# openmv.net
KiCad netlist of a schematic drawn in EAGLE
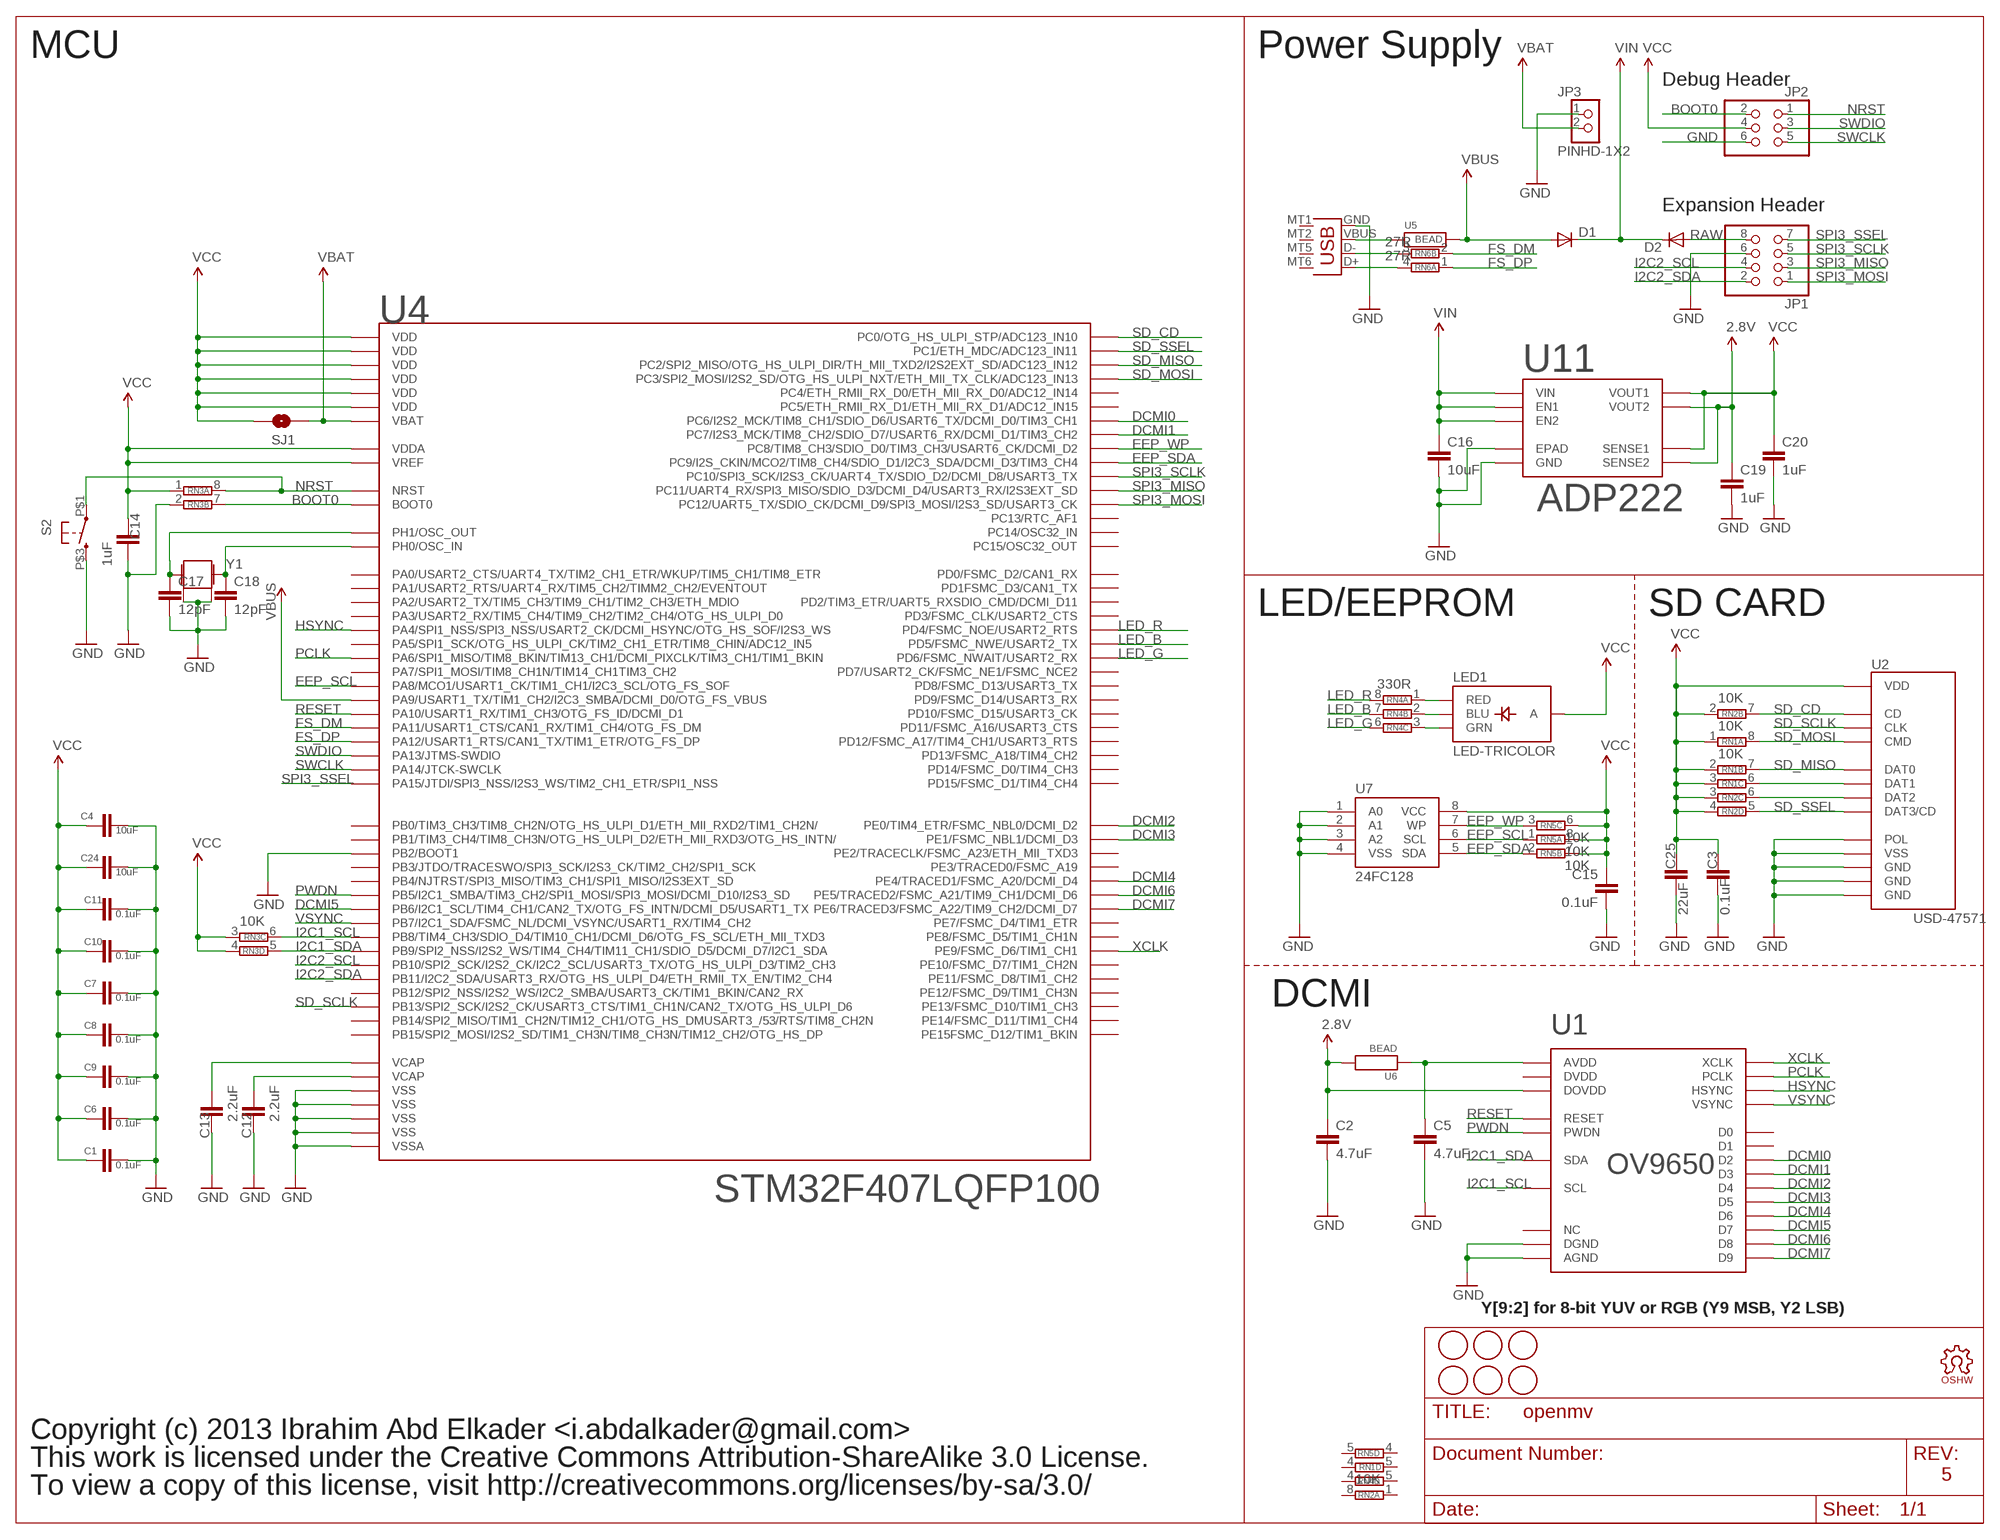
[diagram p0: schematic, sheet 1]

(export (version "E")
  (design (tool "Eeschema 10.0.6"))
  (components
    (comp (ref "C1")
      (value "0.1uF")
      (footprint "eagle-import:0402-CAP")
      (libsource (lib "eagle-import") (part "CAP0402-CAP"))
    )
    (comp (ref "C2")
      (value "4.7uF")
      (footprint "eagle-import:0402-CAP")
      (libsource (lib "eagle-import") (part "CAP0402-CAP"))
    )
    (comp (ref "C3")
      (value "0.1uF")
      (footprint "eagle-import:0402-CAP")
      (libsource (lib "eagle-import") (part "CAP0402-CAP"))
    )
    (comp (ref "C4")
      (value "10uF")
      (footprint "eagle-import:0805")
      (libsource (lib "eagle-import") (part "CAP0805"))
    )
    (comp (ref "C5")
      (value "4.7uF")
      (footprint "eagle-import:0402-CAP")
      (libsource (lib "eagle-import") (part "CAP0402-CAP"))
    )
    (comp (ref "C6")
      (value "0.1uF")
      (footprint "eagle-import:0402-CAP")
      (libsource (lib "eagle-import") (part "CAP0402-CAP"))
    )
    (comp (ref "C7")
      (value "0.1uF")
      (footprint "eagle-import:0402-CAP")
      (libsource (lib "eagle-import") (part "CAP0402-CAP"))
    )
    (comp (ref "C8")
      (value "0.1uF")
      (footprint "eagle-import:0402-CAP")
      (libsource (lib "eagle-import") (part "CAP0402-CAP"))
    )
    (comp (ref "C9")
      (value "0.1uF")
      (footprint "eagle-import:0402-CAP")
      (libsource (lib "eagle-import") (part "CAP0402-CAP"))
    )
    (comp (ref "C10")
      (value "0.1uF")
      (footprint "eagle-import:0402-CAP")
      (libsource (lib "eagle-import") (part "CAP0402-CAP"))
    )
    (comp (ref "C11")
      (value "0.1uF")
      (footprint "eagle-import:0402-CAP")
      (libsource (lib "eagle-import") (part "CAP0402-CAP"))
    )
    (comp (ref "C12")
      (value "2.2uF")
      (footprint "eagle-import:0402-CAP")
      (libsource (lib "eagle-import") (part "CAP0402-CAP"))
    )
    (comp (ref "C13")
      (value "2.2uF")
      (footprint "eagle-import:0402-CAP")
      (libsource (lib "eagle-import") (part "CAP0402-CAP"))
    )
    (comp (ref "C14")
      (value "1uF")
      (footprint "eagle-import:0402-CAP")
      (libsource (lib "eagle-import") (part "CAP0402-CAP"))
    )
    (comp (ref "C15")
      (value "0.1uF")
      (footprint "eagle-import:0402-CAP")
      (libsource (lib "eagle-import") (part "CAP0402-CAP"))
    )
    (comp (ref "C16")
      (value "10uF")
      (footprint "eagle-import:0805")
      (libsource (lib "eagle-import") (part "CAP0805"))
    )
    (comp (ref "C17")
      (value "12pF")
      (footprint "eagle-import:0402-CAP")
      (libsource (lib "eagle-import") (part "CAP0402-CAP"))
    )
    (comp (ref "C18")
      (value "12pF")
      (footprint "eagle-import:0402-CAP")
      (libsource (lib "eagle-import") (part "CAP0402-CAP"))
    )
    (comp (ref "C19")
      (value "1uF")
      (footprint "eagle-import:0402-CAP")
      (libsource (lib "eagle-import") (part "CAP0402-CAP"))
    )
    (comp (ref "C20")
      (value "1uF")
      (footprint "eagle-import:0402-CAP")
      (libsource (lib "eagle-import") (part "CAP0402-CAP"))
    )
    (comp (ref "C24")
      (value "10uF")
      (footprint "eagle-import:0805")
      (libsource (lib "eagle-import") (part "CAP0805"))
    )
    (comp (ref "C25")
      (value "22uF")
      (footprint "eagle-import:0805")
      (libsource (lib "eagle-import") (part "CAP0805"))
    )
    (comp (ref "D1")
      (value "DIODESOD")
      (footprint "eagle-import:SOD-323")
      (libsource (lib "eagle-import") (part "DIODESOD"))
    )
    (comp (ref "D2")
      (value "DIODESOD")
      (footprint "eagle-import:SOD-323")
      (libsource (lib "eagle-import") (part "DIODESOD"))
    )
    (comp (ref "JP1")
      (value "PINHD-2X4")
      (footprint "eagle-import:2X04")
      (libsource (lib "eagle-import") (part "PINHD-2X4"))
    )
    (comp (ref "JP2")
      (value "PINHD-2X3")
      (footprint "eagle-import:2X03")
      (libsource (lib "eagle-import") (part "PINHD-2X3"))
    )
    (comp (ref "JP3")
      (value "PINHD-1X2")
      (footprint "eagle-import:1X2")
      (libsource (lib "eagle-import") (part "PINHD-1X2"))
    )
    (comp (ref "LED1")
      (value "LED-TRICOLOR")
      (footprint "eagle-import:LED-TRICOLOR-SMD")
      (libsource (lib "eagle-import") (part "LED-TRICOLOR"))
    )
    (comp (ref "LOGO1")
      (value "OSHW_LOGO_FILLX0150-NT")
      (footprint "eagle-import:OSHW_FILLX150_NOTEXT")
      (libsource (lib "eagle-import") (part "OSHW_LOGO_FILLX0150-NT"))
    )
    (comp (ref "RN1")
      (value "10K")
      (footprint "eagle-import:CAT16")
      (fields (field (name "OC_FARNELL") "unknown") (field (name "OC_NEWARK") "unknown"))
      (libsource (lib "eagle-import") (part "4R-NCAT16"))
    )
    (comp (ref "RN2")
      (value "10K")
      (footprint "eagle-import:CAT16")
      (fields (field (name "OC_FARNELL") "unknown") (field (name "OC_NEWARK") "unknown"))
      (libsource (lib "eagle-import") (part "4R-NCAT16"))
    )
    (comp (ref "RN3")
      (value "10K")
      (footprint "eagle-import:CAT16")
      (libsource (lib "eagle-import") (part "4R-NCAT16"))
    )
    (comp (ref "RN4")
      (value "330R")
      (footprint "eagle-import:CAT16")
      (fields (field (name "OC_FARNELL") "unknown") (field (name "OC_NEWARK") "unknown"))
      (libsource (lib "eagle-import") (part "4R-NCAT16"))
    )
    (comp (ref "RN5")
      (value "10K")
      (footprint "eagle-import:CAT16")
      (fields (field (name "OC_FARNELL") "unknown") (field (name "OC_NEWARK") "unknown"))
      (libsource (lib "eagle-import") (part "4R-NCAT16"))
    )
    (comp (ref "RN6")
      (value "27R")
      (footprint "eagle-import:EXBV4V")
      (libsource (lib "eagle-import") (part "2R-NEXBV4V"))
    )
    (comp (ref "S2")
      (value "SWITCHKMR442G")
      (footprint "eagle-import:KMR442G")
      (libsource (lib "eagle-import") (part "SWITCHKMR442G"))
    )
    (comp (ref "SJ1")
      (value "SOLDERJUMPERTRACE")
      (footprint "eagle-import:SJ_2S-TRACE")
      (libsource (lib "eagle-import") (part "SOLDERJUMPERTRACE"))
    )
    (comp (ref "U$3")
      (value "FIDUCIAL")
      (footprint "eagle-import:FIDUCIAL_1MM")
      (libsource (lib "eagle-import") (part "FIDUCIAL"))
    )
    (comp (ref "U$4")
      (value "FIDUCIAL")
      (footprint "eagle-import:FIDUCIAL_1MM")
      (libsource (lib "eagle-import") (part "FIDUCIAL"))
    )
    (comp (ref "U$5")
      (value "FIDUCIAL")
      (footprint "eagle-import:FIDUCIAL_1MM")
      (libsource (lib "eagle-import") (part "FIDUCIAL"))
    )
    (comp (ref "U$7")
      (value "FIDUCIAL")
      (footprint "eagle-import:FIDUCIAL_1MM")
      (libsource (lib "eagle-import") (part "FIDUCIAL"))
    )
    (comp (ref "U$9")
      (value "FIDUCIAL")
      (footprint "eagle-import:FIDUCIAL_1MM")
      (libsource (lib "eagle-import") (part "FIDUCIAL"))
    )
    (comp (ref "U$10")
      (value "FIDUCIAL")
      (footprint "eagle-import:FIDUCIAL_1MM")
      (libsource (lib "eagle-import") (part "FIDUCIAL"))
    )
    (comp (ref "U1")
      (value "OV9650")
      (footprint "eagle-import:OV9650")
      (libsource (lib "eagle-import") (part "OV9650"))
    )
    (comp (ref "U2")
      (value "USD-47571")
      (footprint "eagle-import:USD-47571")
      (libsource (lib "eagle-import") (part "USD-47571"))
    )
    (comp (ref "U4")
      (value "STM32F407LQFP100")
      (footprint "eagle-import:LQFP100")
      (libsource (lib "eagle-import") (part "STM32F407LQFP100"))
    )
    (comp (ref "U5")
      (value "BEAD")
      (footprint "eagle-import:0402-CAP")
      (libsource (lib "eagle-import") (part "BEAD"))
    )
    (comp (ref "U6")
      (value "BEAD")
      (footprint "eagle-import:0402-CAP")
      (libsource (lib "eagle-import") (part "BEAD"))
    )
    (comp (ref "U7")
      (value "24FC128")
      (footprint "eagle-import:MSOP8")
      (libsource (lib "eagle-import") (part "24FC128"))
    )
    (comp (ref "U11")
      (value "ADP222")
      (footprint "eagle-import:LFCSP8")
      (libsource (lib "eagle-import") (part "ADP222"))
    )
    (comp (ref "X1")
      (value "USB-MICROB")
      (footprint "eagle-import:USB-MICROB")
      (libsource (lib "eagle-import") (part "USB-MICROB"))
    )
    (comp (ref "Y1")
      (value "CRYSTAL2.5X2.0")
      (footprint "eagle-import:CRYSTAL-2.5X2.0")
      (libsource (lib "eagle-import") (part "CRYSTAL2.5X2.0"))
    )
  )
  (nets
    (net (code "1") (name "/BOOT0") (class "Default")
      (node (ref "JP2") (pin "2") (pinfunction "2_2") (pintype "passive"))
      (node (ref "RN3") (pin "7") (pinfunction "2_7") (pintype "passive"))
      (node (ref "U4") (pin "94") (pinfunction "BOOT0_94") (pintype "bidirectional"))
    )
    (net (code "2") (name "/DCMI0") (class "Default")
      (node (ref "U1") (pin "P$19") (pinfunction "D2_P$19") (pintype "bidirectional"))
      (node (ref "U4") (pin "63") (pinfunction "PC6/I2S2_MCK/TIM8_CH1/SDIO_D6/USART6_TX/DCMI_D0/TIM3_CH1_63") (pintype "bidirectional"))
    )
    (net (code "3") (name "/DCMI1") (class "Default")
      (node (ref "U1") (pin "P$21") (pinfunction "D3_P$21") (pintype "bidirectional"))
      (node (ref "U4") (pin "64") (pinfunction "PC7/I2S3_MCK/TIM8_CH2/SDIO_D7/USART6_RX/DCMI_D1/TIM3_CH2_64") (pintype "bidirectional"))
    )
    (net (code "4") (name "/DCMI2") (class "Default")
      (node (ref "U1") (pin "P$22") (pinfunction "D4_P$22") (pintype "bidirectional"))
      (node (ref "U4") (pin "97") (pinfunction "PE0/TIM4_ETR/FSMC_NBL0/DCMI_D2_97") (pintype "bidirectional"))
    )
    (net (code "5") (name "/DCMI3") (class "Default")
      (node (ref "U1") (pin "P$20") (pinfunction "D5_P$20") (pintype "bidirectional"))
      (node (ref "U4") (pin "98") (pinfunction "PE1/FSMC_NBL1/DCMI_D3_98") (pintype "bidirectional"))
    )
    (net (code "6") (name "/DCMI4") (class "Default")
      (node (ref "U1") (pin "P$18") (pinfunction "D6_P$18") (pintype "bidirectional"))
      (node (ref "U4") (pin "3") (pinfunction "PE4/TRACED1/FSMC_A20/DCMI_D4_3") (pintype "bidirectional"))
    )
    (net (code "7") (name "/DCMI5") (class "Default")
      (node (ref "U1") (pin "P$16") (pinfunction "D7_P$16") (pintype "bidirectional"))
      (node (ref "U4") (pin "92") (pinfunction "PB6/I2C1_SCL/TIM4_CH1/CAN2_TX/OTG_FS_INTN/DCMI_D5/USART1_TX_92") (pintype "bidirectional"))
    )
    (net (code "8") (name "/DCMI6") (class "Default")
      (node (ref "U1") (pin "P$14") (pinfunction "D8_P$14") (pintype "bidirectional"))
      (node (ref "U4") (pin "4") (pinfunction "PE5/TRACED2/FSMC_A21/TIM9_CH1/DCMI_D6_4") (pintype "bidirectional"))
    )
    (net (code "9") (name "/DCMI7") (class "Default")
      (node (ref "U1") (pin "P$12") (pinfunction "D9_P$12") (pintype "bidirectional"))
      (node (ref "U4") (pin "5") (pinfunction "PE6/TRACED3/FSMC_A22/TIM9_CH2/DCMI_D7_5") (pintype "bidirectional"))
    )
    (net (code "10") (name "/EEP_SCL") (class "Default")
      (node (ref "RN5") (pin "1") (pinfunction "1_1") (pintype "passive"))
      (node (ref "U4") (pin "67") (pinfunction "PA8/MCO1/USART1_CK/TIM1_CH1/I2C3_SCL/OTG_FS_SOF_67") (pintype "bidirectional"))
      (node (ref "U7") (pin "6") (pinfunction "SCL_6") (pintype "bidirectional"))
    )
    (net (code "11") (name "/EEP_SDA") (class "Default")
      (node (ref "RN5") (pin "2") (pinfunction "1_2") (pintype "passive"))
      (node (ref "U4") (pin "66") (pinfunction "PC9/I2S_CKIN/MCO2/TIM8_CH4/SDIO_D1/I2C3_SDA/DCMI_D3/TIM3_CH4_66") (pintype "bidirectional"))
      (node (ref "U7") (pin "5") (pinfunction "SDA_5") (pintype "bidirectional"))
    )
    (net (code "12") (name "/EEP_WP") (class "Default")
      (node (ref "RN5") (pin "3") (pinfunction "1_3") (pintype "passive"))
      (node (ref "U4") (pin "65") (pinfunction "PC8/TIM8_CH3/SDIO_D0/TIM3_CH3/USART6_CK/DCMI_D2_65") (pintype "bidirectional"))
      (node (ref "U7") (pin "7") (pinfunction "WP_7") (pintype "bidirectional"))
    )
    (net (code "13") (name "/FS_DM") (class "Default")
      (node (ref "RN6") (pin "2") (pinfunction "1_2") (pintype "passive"))
      (node (ref "U4") (pin "70") (pinfunction "PA11/USART1_CTS/CAN1_RX/TIM1_CH4/OTG_FS_DM_70") (pintype "bidirectional"))
    )
    (net (code "14") (name "/FS_DP") (class "Default")
      (node (ref "RN6") (pin "1") (pinfunction "1_1") (pintype "passive"))
      (node (ref "U4") (pin "71") (pinfunction "PA12/USART1_RTS/CAN1_TX/TIM1_ETR/OTG_FS_DP_71") (pintype "bidirectional"))
    )
    (net (code "15") (name "/HSYNC") (class "Default")
      (node (ref "U1") (pin "P$9") (pinfunction "HSYNC_P$9") (pintype "bidirectional"))
      (node (ref "U4") (pin "29") (pinfunction "PA4/SPI1_NSS/SPI3_NSS/USART2_CK/DCMI_HSYNC/OTG_HS_SOF/I2S3_WS_29") (pintype "bidirectional"))
    )
    (net (code "16") (name "/I2C1_SCL") (class "Default")
      (node (ref "RN3") (pin "6") (pinfunction "2_6") (pintype "passive"))
      (node (ref "U1") (pin "P$5") (pinfunction "SCL_P$5") (pintype "bidirectional"))
      (node (ref "U4") (pin "95") (pinfunction "PB8/TIM4_CH3/SDIO_D4/TIM10_CH1/DCMI_D6/OTG_FS_SCL/ETH_MII_TXD3_95") (pintype "bidirectional"))
    )
    (net (code "17") (name "/I2C1_SDA") (class "Default")
      (node (ref "RN3") (pin "5") (pinfunction "2_5") (pintype "passive"))
      (node (ref "U1") (pin "P$3") (pinfunction "SDA_P$3") (pintype "bidirectional"))
      (node (ref "U4") (pin "96") (pinfunction "PB9/SPI2_NSS/I2S2_WS/TIM4_CH4/TIM11_CH1/SDIO_D5/DCMI_D7/I2C1_SDA_96") (pintype "bidirectional"))
    )
    (net (code "18") (name "/I2C2_SCL") (class "Default")
      (node (ref "JP1") (pin "4") (pinfunction "4_4") (pintype "passive"))
      (node (ref "U4") (pin "47") (pinfunction "PB10/SPI2_SCK/I2S2_CK/I2C2_SCL/USART3_TX/OTG_HS_ULPI_D3/TIM2_CH3_47") (pintype "bidirectional"))
    )
    (net (code "19") (name "/I2C2_SDA") (class "Default")
      (node (ref "JP1") (pin "2") (pinfunction "2_2") (pintype "passive"))
      (node (ref "U4") (pin "48") (pinfunction "PB11/I2C2_SDA/USART3_RX/OTG_HS_ULPI_D4/ETH_RMII_TX_EN/TIM2_CH4_48") (pintype "bidirectional"))
    )
    (net (code "20") (name "/LED_B") (class "Default")
      (node (ref "RN4") (pin "7") (pinfunction "2_7") (pintype "passive"))
      (node (ref "U4") (pin "86") (pinfunction "PD5/FSMC_NWE/USART2_TX_86") (pintype "bidirectional"))
    )
    (net (code "21") (name "/LED_G") (class "Default")
      (node (ref "RN4") (pin "6") (pinfunction "2_6") (pintype "passive"))
      (node (ref "U4") (pin "87") (pinfunction "PD6/FSMC_NWAIT/USART2_RX_87") (pintype "bidirectional"))
    )
    (net (code "22") (name "/LED_R") (class "Default")
      (node (ref "RN4") (pin "8") (pinfunction "2_8") (pintype "passive"))
      (node (ref "U4") (pin "85") (pinfunction "PD4/FSMC_NOE/USART2_RTS_85") (pintype "bidirectional"))
    )
    (net (code "23") (name "/NRST") (class "Default")
      (node (ref "JP2") (pin "1") (pinfunction "1_1") (pintype "passive"))
      (node (ref "RN3") (pin "8") (pinfunction "2_8") (pintype "passive"))
      (node (ref "S2") (pin "P$1") (pinfunction "1_P$1") (pintype "passive"))
      (node (ref "U4") (pin "14") (pinfunction "NRST_14") (pintype "bidirectional"))
    )
    (net (code "24") (name "/PCLK") (class "Default")
      (node (ref "U1") (pin "P$17") (pinfunction "PCLK_P$17") (pintype "bidirectional"))
      (node (ref "U4") (pin "31") (pinfunction "PA6/SPI1_MISO/TIM8_BKIN/TIM13_CH1/DCMI_PIXCLK/TIM3_CH1/TIM1_BKIN_31") (pintype "bidirectional"))
    )
    (net (code "25") (name "/PWDN") (class "Default")
      (node (ref "U1") (pin "P$8") (pinfunction "PWDN_P$8") (pintype "bidirectional"))
      (node (ref "U4") (pin "91") (pinfunction "PB5/I2C1_SMBA/TIM3_CH2/SPI1_MOSI/SPI3_MOSI/DCMI_D10/I2S3_SD_91") (pintype "bidirectional"))
    )
    (net (code "26") (name "/RAW") (class "Default")
      (node (ref "D2") (pin "2") (pinfunction "A_2") (pintype "passive"))
      (node (ref "JP1") (pin "8") (pinfunction "8_8") (pintype "passive"))
    )
    (net (code "27") (name "/RESET") (class "Default")
      (node (ref "U1") (pin "P$6") (pinfunction "RESET_P$6") (pintype "bidirectional"))
      (node (ref "U4") (pin "69") (pinfunction "PA10/USART1_RX/TIM1_CH3/OTG_FS_ID/DCMI_D1_69") (pintype "bidirectional"))
    )
    (net (code "28") (name "/SD_CD") (class "Default")
      (node (ref "RN2") (pin "7") (pinfunction "2_7") (pintype "passive"))
      (node (ref "U2") (pin "G$5") (pinfunction "CD_G$5") (pintype "power_in"))
      (node (ref "U4") (pin "15") (pinfunction "PC0/OTG_HS_ULPI_STP/ADC123_IN10_15") (pintype "bidirectional"))
    )
    (net (code "29") (name "/SD_MISO") (class "Default")
      (node (ref "RN1") (pin "7") (pinfunction "2_7") (pintype "passive"))
      (node (ref "U2") (pin "P$7") (pinfunction "DAT0_P$7") (pintype "bidirectional"))
      (node (ref "U4") (pin "17") (pinfunction "PC2/SPI2_MISO/OTG_HS_ULPI_DIR/TH_MII_TXD2/I2S2EXT_SD/ADC123_IN12_17") (pintype "bidirectional"))
    )
    (net (code "30") (name "/SD_MOSI") (class "Default")
      (node (ref "RN1") (pin "8") (pinfunction "2_8") (pintype "passive"))
      (node (ref "U2") (pin "P$3") (pinfunction "CMD_P$3") (pintype "bidirectional"))
      (node (ref "U4") (pin "18") (pinfunction "PC3/SPI2_MOSI/I2S2_SD/OTG_HS_ULPI_NXT/ETH_MII_TX_CLK/ADC123_IN13_18") (pintype "bidirectional"))
    )
    (net (code "31") (name "/SD_SCLK") (class "Default")
      (node (ref "U2") (pin "P$5") (pinfunction "CLK_P$5") (pintype "bidirectional"))
      (node (ref "U4") (pin "52") (pinfunction "PB13/SPI2_SCK/I2S2_CK/USART3_CTS/TIM1_CH1N/CAN2_TX/OTG_HS_ULPI_D6_52") (pintype "bidirectional"))
    )
    (net (code "32") (name "/SD_SSEL") (class "Default")
      (node (ref "RN2") (pin "5") (pinfunction "2_5") (pintype "passive"))
      (node (ref "U2") (pin "P$2") (pinfunction "DAT3/CD_P$2") (pintype "bidirectional"))
      (node (ref "U4") (pin "16") (pinfunction "PC1/ETH_MDC/ADC123_IN11_16") (pintype "bidirectional"))
    )
    (net (code "33") (name "/SPI3_MISO") (class "Default")
      (node (ref "JP1") (pin "3") (pinfunction "3_3") (pintype "passive"))
      (node (ref "U4") (pin "79") (pinfunction "PC11/UART4_RX/SPI3_MISO/SDIO_D3/DCMI_D4/USART3_RX/I2S3EXT_SD_79") (pintype "bidirectional"))
    )
    (net (code "34") (name "/SPI3_MOSI") (class "Default")
      (node (ref "JP1") (pin "1") (pinfunction "1_1") (pintype "passive"))
      (node (ref "U4") (pin "80") (pinfunction "PC12/UART5_TX/SDIO_CK/DCMI_D9/SPI3_MOSI/I2S3_SD/USART3_CK_80") (pintype "bidirectional"))
    )
    (net (code "35") (name "/SPI3_SCLK") (class "Default")
      (node (ref "JP1") (pin "5") (pinfunction "5_5") (pintype "passive"))
      (node (ref "U4") (pin "78") (pinfunction "PC10/SPI3_SCK/I2S3_CK/UART4_TX/SDIO_D2/DCMI_D8/USART3_TX_78") (pintype "bidirectional"))
    )
    (net (code "36") (name "/SPI3_SSEL") (class "Default")
      (node (ref "JP1") (pin "7") (pinfunction "7_7") (pintype "passive"))
      (node (ref "U4") (pin "77") (pinfunction "PA15/JTDI/SPI3_NSS/I2S3_WS/TIM2_CH1_ETR/SPI1_NSS_77") (pintype "bidirectional"))
    )
    (net (code "37") (name "/SWCLK") (class "Default")
      (node (ref "JP2") (pin "5") (pinfunction "5_5") (pintype "passive"))
      (node (ref "U4") (pin "76") (pinfunction "PA14/JTCK-SWCLK_76") (pintype "bidirectional"))
    )
    (net (code "38") (name "/SWDIO") (class "Default")
      (node (ref "JP2") (pin "3") (pinfunction "3_3") (pintype "passive"))
      (node (ref "U4") (pin "72") (pinfunction "PA13/JTMS-SWDIO_72") (pintype "bidirectional"))
    )
    (net (code "39") (name "/VSYNC") (class "Default")
      (node (ref "U1") (pin "P$7") (pinfunction "VSYNC_P$7") (pintype "bidirectional"))
      (node (ref "U4") (pin "93") (pinfunction "PB7/I2C1_SDA/FSMC_NL/DCMI_VSYNC/USART1_RX/TIM4_CH2_93") (pintype "bidirectional"))
    )
    (net (code "40") (name "/XCLK") (class "Default")
      (node (ref "U1") (pin "P$13") (pinfunction "XCLK_P$13") (pintype "bidirectional"))
      (node (ref "U4") (pin "40") (pinfunction "PE9/FSMC_D6/TIM1_CH1_40") (pintype "bidirectional"))
    )
    (net (code "41") (name "2.8V") (class "Default")
      (node (ref "C19") (pin "1") (pinfunction "1_1") (pintype "passive"))
      (node (ref "C2") (pin "1") (pinfunction "1_1") (pintype "passive"))
      (node (ref "U1") (pin "P$11") (pinfunction "DOVDD_P$11") (pintype "bidirectional"))
      (node (ref "U11") (pin "4") (pinfunction "SENSE2_4") (pintype "passive"))
      (node (ref "U11") (pin "5") (pinfunction "VOUT2_5") (pintype "passive"))
      (node (ref "U6") (pin "2") (pinfunction "2_2") (pintype "passive"))
    )
    (net (code "42") (name "GND") (class "Default")
      (node (ref "C1") (pin "1") (pinfunction "1_1") (pintype "passive"))
      (node (ref "C10") (pin "2") (pinfunction "2_2") (pintype "passive"))
      (node (ref "C11") (pin "2") (pinfunction "2_2") (pintype "passive"))
      (node (ref "C12") (pin "2") (pinfunction "2_2") (pintype "passive"))
      (node (ref "C13") (pin "2") (pinfunction "2_2") (pintype "passive"))
      (node (ref "C14") (pin "1") (pinfunction "1_1") (pintype "passive"))
      (node (ref "C15") (pin "2") (pinfunction "2_2") (pintype "passive"))
      (node (ref "C16") (pin "2") (pinfunction "2_2") (pintype "passive"))
      (node (ref "C17") (pin "2") (pinfunction "2_2") (pintype "passive"))
      (node (ref "C18") (pin "2") (pinfunction "2_2") (pintype "passive"))
      (node (ref "C19") (pin "2") (pinfunction "2_2") (pintype "passive"))
      (node (ref "C2") (pin "2") (pinfunction "2_2") (pintype "passive"))
      (node (ref "C20") (pin "2") (pinfunction "2_2") (pintype "passive"))
      (node (ref "C24") (pin "1") (pinfunction "1_1") (pintype "passive"))
      (node (ref "C25") (pin "2") (pinfunction "2_2") (pintype "passive"))
      (node (ref "C3") (pin "2") (pinfunction "2_2") (pintype "passive"))
      (node (ref "C4") (pin "1") (pinfunction "1_1") (pintype "passive"))
      (node (ref "C5") (pin "2") (pinfunction "2_2") (pintype "passive"))
      (node (ref "C6") (pin "1") (pinfunction "1_1") (pintype "passive"))
      (node (ref "C7") (pin "2") (pinfunction "2_2") (pintype "passive"))
      (node (ref "C8") (pin "1") (pinfunction "1_1") (pintype "passive"))
      (node (ref "C9") (pin "1") (pinfunction "1_1") (pintype "passive"))
      (node (ref "JP1") (pin "6") (pinfunction "6_6") (pintype "passive"))
      (node (ref "JP2") (pin "6") (pinfunction "6_6") (pintype "passive"))
      (node (ref "JP3") (pin "1") (pinfunction "1_1") (pintype "passive"))
      (node (ref "RN3") (pin "2") (pinfunction "1_2") (pintype "passive"))
      (node (ref "S2") (pin "P$3") (pinfunction "2_P$3") (pintype "passive"))
      (node (ref "U1") (pin "P$15") (pinfunction "DGND_P$15") (pintype "bidirectional"))
      (node (ref "U1") (pin "P$2") (pinfunction "AGND_P$2") (pintype "power_in"))
      (node (ref "U11") (pin "3") (pinfunction "GND_3") (pintype "power_in"))
      (node (ref "U11") (pin "EXP") (pinfunction "EPAD_EXP") (pintype "input"))
      (node (ref "U2") (pin "G$1") (pinfunction "GND_G$1") (pintype "power_in"))
      (node (ref "U2") (pin "G$2") (pinfunction "GND_G$2") (pintype "power_in"))
      (node (ref "U2") (pin "G$3") (pinfunction "GND_G$3") (pintype "power_in"))
      (node (ref "U2") (pin "G$4") (pinfunction "POL_G$4") (pintype "power_in"))
      (node (ref "U2") (pin "P$6") (pinfunction "VSS_P$6") (pintype "power_in"))
      (node (ref "U4") (pin "10") (pinfunction "VSS_10") (pintype "power_in"))
      (node (ref "U4") (pin "20") (pinfunction "VSSA_20") (pintype "power_in"))
      (node (ref "U4") (pin "27") (pinfunction "VSS_27") (pintype "power_in"))
      (node (ref "U4") (pin "37") (pinfunction "PB2/BOOT1_37") (pintype "bidirectional"))
      (node (ref "U4") (pin "74") (pinfunction "VSS_74") (pintype "power_in"))
      (node (ref "U4") (pin "99") (pinfunction "VSS_99") (pintype "power_in"))
      (node (ref "U7") (pin "1") (pinfunction "A0_1") (pintype "bidirectional"))
      (node (ref "U7") (pin "2") (pinfunction "A1_2") (pintype "bidirectional"))
      (node (ref "U7") (pin "3") (pinfunction "A2_3") (pintype "bidirectional"))
      (node (ref "U7") (pin "4") (pinfunction "VSS_4") (pintype "power_in"))
      (node (ref "X1") (pin "GND") (pinfunction "GND_GND") (pintype "bidirectional"))
      (node (ref "Y1") (pin "2") (pinfunction "P$1_2") (pintype "power_in"))
      (node (ref "Y1") (pin "4") (pinfunction "P$2_4") (pintype "power_in"))
    )
    (net (code "43") (name "Net-(C12-Pad1)") (class "Default")
      (node (ref "C12") (pin "1") (pinfunction "1_1") (pintype "passive"))
      (node (ref "U4") (pin "73") (pinfunction "VCAP_73") (pintype "power_in"))
    )
    (net (code "44") (name "Net-(C13-Pad1)") (class "Default")
      (node (ref "C13") (pin "1") (pinfunction "1_1") (pintype "passive"))
      (node (ref "U4") (pin "49") (pinfunction "VCAP_49") (pintype "power_in"))
    )
    (net (code "45") (name "Net-(LED1-BLU)") (class "Default")
      (node (ref "LED1") (pin "B") (pinfunction "BLU_B") (pintype "bidirectional"))
      (node (ref "RN4") (pin "2") (pinfunction "1_2") (pintype "passive"))
    )
    (net (code "46") (name "Net-(LED1-GRN)") (class "Default")
      (node (ref "LED1") (pin "G") (pinfunction "GRN_G") (pintype "bidirectional"))
      (node (ref "RN4") (pin "3") (pinfunction "1_3") (pintype "passive"))
    )
    (net (code "47") (name "Net-(LED1-RED)") (class "Default")
      (node (ref "LED1") (pin "R") (pinfunction "RED_R") (pintype "bidirectional"))
      (node (ref "RN4") (pin "1") (pinfunction "1_1") (pintype "passive"))
    )
    (net (code "48") (name "Net-(RN1C-2)") (class "Default")
      (node (ref "RN1") (pin "6") (pinfunction "2_6") (pintype "passive"))
      (node (ref "U2") (pin "P$8") (pinfunction "DAT1_P$8") (pintype "bidirectional"))
    )
    (net (code "49") (name "Net-(RN2C-2)") (class "Default")
      (node (ref "RN2") (pin "6") (pinfunction "2_6") (pintype "passive"))
      (node (ref "U2") (pin "P$1") (pinfunction "DAT2_P$1") (pintype "bidirectional"))
    )
    (net (code "50") (name "Net-(RN6A-2)") (class "Default")
      (node (ref "RN6") (pin "4") (pinfunction "2_4") (pintype "passive"))
      (node (ref "X1") (pin "D+") (pinfunction "D+_D+") (pintype "bidirectional"))
    )
    (net (code "51") (name "Net-(RN6B-2)") (class "Default")
      (node (ref "RN6") (pin "3") (pinfunction "2_3") (pintype "passive"))
      (node (ref "X1") (pin "D-") (pinfunction "D-_D-") (pintype "bidirectional"))
    )
    (net (code "52") (name "Net-(U1-AVDD)") (class "Default")
      (node (ref "C5") (pin "1") (pinfunction "1_1") (pintype "passive"))
      (node (ref "U1") (pin "P$4") (pinfunction "AVDD_P$4") (pintype "power_in"))
      (node (ref "U6") (pin "1") (pinfunction "1_1") (pintype "passive"))
    )
    (net (code "53") (name "Net-(U4-PH0{slash}OSC_IN)") (class "Default")
      (node (ref "C18") (pin "1") (pinfunction "1_1") (pintype "passive"))
      (node (ref "U4") (pin "12") (pinfunction "PH0/OSC_IN_12") (pintype "bidirectional"))
      (node (ref "Y1") (pin "1") (pinfunction "1_1") (pintype "passive"))
    )
    (net (code "54") (name "Net-(U4-PH1{slash}OSC_OUT)") (class "Default")
      (node (ref "C17") (pin "1") (pinfunction "1_1") (pintype "passive"))
      (node (ref "U4") (pin "13") (pinfunction "PH1/OSC_OUT_13") (pintype "bidirectional"))
      (node (ref "Y1") (pin "3") (pinfunction "2_3") (pintype "passive"))
    )
    (net (code "55") (name "Net-(U5-Pad1)") (class "Default")
      (node (ref "U5") (pin "1") (pinfunction "1_1") (pintype "passive"))
      (node (ref "X1") (pin "VBUS") (pinfunction "VBUS_VBUS") (pintype "bidirectional"))
    )
    (net (code "56") (name "VBAT") (class "Default")
      (node (ref "JP3") (pin "2") (pinfunction "2_2") (pintype "passive"))
      (node (ref "SJ1") (pin "1") (pinfunction "1_1") (pintype "passive"))
      (node (ref "U4") (pin "6") (pinfunction "VBAT_6") (pintype "power_in"))
    )
    (net (code "57") (name "VBUS") (class "Default")
      (node (ref "D1") (pin "2") (pinfunction "A_2") (pintype "passive"))
      (node (ref "U4") (pin "68") (pinfunction "PA9/USART1_TX/TIM1_CH2/I2C3_SMBA/DCMI_D0/OTG_FS_VBUS_68") (pintype "bidirectional"))
      (node (ref "U5") (pin "2") (pinfunction "2_2") (pintype "passive"))
    )
    (net (code "58") (name "VCC") (class "Default")
      (node (ref "C1") (pin "2") (pinfunction "2_2") (pintype "passive"))
      (node (ref "C10") (pin "1") (pinfunction "1_1") (pintype "passive"))
      (node (ref "C11") (pin "1") (pinfunction "1_1") (pintype "passive"))
      (node (ref "C14") (pin "2") (pinfunction "2_2") (pintype "passive"))
      (node (ref "C15") (pin "1") (pinfunction "1_1") (pintype "passive"))
      (node (ref "C20") (pin "1") (pinfunction "1_1") (pintype "passive"))
      (node (ref "C24") (pin "2") (pinfunction "2_2") (pintype "passive"))
      (node (ref "C25") (pin "1") (pinfunction "1_1") (pintype "passive"))
      (node (ref "C3") (pin "1") (pinfunction "1_1") (pintype "passive"))
      (node (ref "C4") (pin "2") (pinfunction "2_2") (pintype "passive"))
      (node (ref "C6") (pin "2") (pinfunction "2_2") (pintype "passive"))
      (node (ref "C7") (pin "1") (pinfunction "1_1") (pintype "passive"))
      (node (ref "C8") (pin "2") (pinfunction "2_2") (pintype "passive"))
      (node (ref "C9") (pin "2") (pinfunction "2_2") (pintype "passive"))
      (node (ref "JP2") (pin "4") (pinfunction "4_4") (pintype "passive"))
      (node (ref "LED1") (pin "A") (pinfunction "A_A") (pintype "bidirectional"))
      (node (ref "RN1") (pin "1") (pinfunction "1_1") (pintype "passive"))
      (node (ref "RN1") (pin "2") (pinfunction "1_2") (pintype "passive"))
      (node (ref "RN1") (pin "3") (pinfunction "1_3") (pintype "passive"))
      (node (ref "RN2") (pin "2") (pinfunction "1_2") (pintype "passive"))
      (node (ref "RN2") (pin "3") (pinfunction "1_3") (pintype "passive"))
      (node (ref "RN2") (pin "4") (pinfunction "1_4") (pintype "passive"))
      (node (ref "RN3") (pin "1") (pinfunction "1_1") (pintype "passive"))
      (node (ref "RN3") (pin "3") (pinfunction "1_3") (pintype "passive"))
      (node (ref "RN3") (pin "4") (pinfunction "1_4") (pintype "passive"))
      (node (ref "RN5") (pin "6") (pinfunction "2_6") (pintype "passive"))
      (node (ref "RN5") (pin "7") (pinfunction "2_7") (pintype "passive"))
      (node (ref "RN5") (pin "8") (pinfunction "2_8") (pintype "passive"))
      (node (ref "SJ1") (pin "2") (pinfunction "2_2") (pintype "passive"))
      (node (ref "U11") (pin "7") (pinfunction "VOUT1_7") (pintype "passive"))
      (node (ref "U11") (pin "8") (pinfunction "SENSE1_8") (pintype "passive"))
      (node (ref "U2") (pin "P$4") (pinfunction "VDD_P$4") (pintype "power_in"))
      (node (ref "U4") (pin "100") (pinfunction "VDD_100") (pintype "power_in"))
      (node (ref "U4") (pin "11") (pinfunction "VDD_11") (pintype "power_in"))
      (node (ref "U4") (pin "19") (pinfunction "VDD_19") (pintype "power_in"))
      (node (ref "U4") (pin "21") (pinfunction "VREF_21") (pintype "power_in"))
      (node (ref "U4") (pin "22") (pinfunction "VDDA_22") (pintype "power_in"))
      (node (ref "U4") (pin "28") (pinfunction "VDD_28") (pintype "power_in"))
      (node (ref "U4") (pin "50") (pinfunction "VDD_50") (pintype "power_in"))
      (node (ref "U4") (pin "75") (pinfunction "VDD_75") (pintype "power_in"))
      (node (ref "U7") (pin "8") (pinfunction "VCC_8") (pintype "power_in"))
    )
    (net (code "59") (name "VIN") (class "Default")
      (node (ref "C16") (pin "1") (pinfunction "1_1") (pintype "passive"))
      (node (ref "D1") (pin "1") (pinfunction "C_1") (pintype "passive"))
      (node (ref "D2") (pin "1") (pinfunction "C_1") (pintype "passive"))
      (node (ref "U11") (pin "1") (pinfunction "EN1_1") (pintype "input"))
      (node (ref "U11") (pin "2") (pinfunction "EN2_2") (pintype "input"))
      (node (ref "U11") (pin "6") (pinfunction "VIN_6") (pintype "power_in"))
    )
    (net (code "60") (name "unconnected-(RN1D-1-Pad4)") (class "Default")
      (node (ref "RN1") (pin "4") (pinfunction "1_4") (pintype "passive"))
    )
    (net (code "61") (name "unconnected-(RN1D-2-Pad5)") (class "Default")
      (node (ref "RN1") (pin "5") (pinfunction "2_5") (pintype "passive"))
    )
    (net (code "62") (name "unconnected-(RN2-Pad1)") (class "Default")
      (node (ref "RN2") (pin "1") (pinfunction "1_1") (pintype "passive"))
    )
    (net (code "63") (name "unconnected-(RN2A-2-Pad8)") (class "Default")
      (node (ref "RN2") (pin "8") (pinfunction "2_8") (pintype "passive"))
    )
    (net (code "64") (name "unconnected-(RN4D-1-Pad4)") (class "Default")
      (node (ref "RN4") (pin "4") (pinfunction "1_4") (pintype "passive"))
    )
    (net (code "65") (name "unconnected-(RN4D-2-Pad5)") (class "Default")
      (node (ref "RN4") (pin "5") (pinfunction "2_5") (pintype "passive"))
    )
    (net (code "66") (name "unconnected-(RN5D-1-Pad4)") (class "Default")
      (node (ref "RN5") (pin "4") (pinfunction "1_4") (pintype "passive"))
    )
    (net (code "67") (name "unconnected-(RN5D-2-Pad5)") (class "Default")
      (node (ref "RN5") (pin "5") (pinfunction "2_5") (pintype "passive"))
    )
    (net (code "68") (name "unconnected-(U1-D0-PadP$24)") (class "Default")
      (node (ref "U1") (pin "P$24") (pinfunction "D0_P$24") (pintype "bidirectional"))
    )
    (net (code "69") (name "unconnected-(U1-D1-PadP$23)") (class "Default")
      (node (ref "U1") (pin "P$23") (pinfunction "D1_P$23") (pintype "bidirectional"))
    )
    (net (code "70") (name "unconnected-(U1-DVDD-PadP$10)") (class "Default")
      (node (ref "U1") (pin "P$10") (pinfunction "DVDD_P$10") (pintype "bidirectional"))
    )
    (net (code "71") (name "unconnected-(U1-NC-PadP$1)") (class "Default")
      (node (ref "U1") (pin "P$1") (pinfunction "NC_P$1") (pintype "no_connect"))
    )
    (net (code "72") (name "unconnected-(U4-PA0{slash}USART2_CTS{slash}UART4_TX{slash}TIM2_CH1_ETR{slash}WKUP{slash}TIM5_CH1{slash}TIM8_ETR-Pad23)") (class "Default")
      (node (ref "U4") (pin "23") (pinfunction "PA0/USART2_CTS/UART4_TX/TIM2_CH1_ETR/WKUP/TIM5_CH1/TIM8_ETR_23") (pintype "bidirectional"))
    )
    (net (code "73") (name "unconnected-(U4-PA1{slash}USART2_RTS{slash}UART4_RX{slash}TIM5_CH2{slash}TIMM2_CH2{slash}EVENTOUT-Pad24)") (class "Default")
      (node (ref "U4") (pin "24") (pinfunction "PA1/USART2_RTS/UART4_RX/TIM5_CH2/TIMM2_CH2/EVENTOUT_24") (pintype "bidirectional"))
    )
    (net (code "74") (name "unconnected-(U4-PA2{slash}USART2_TX{slash}TIM5_CH3{slash}TIM9_CH1{slash}TIM2_CH3{slash}ETH_MDIO-Pad25)") (class "Default")
      (node (ref "U4") (pin "25") (pinfunction "PA2/USART2_TX/TIM5_CH3/TIM9_CH1/TIM2_CH3/ETH_MDIO_25") (pintype "bidirectional"))
    )
    (net (code "75") (name "unconnected-(U4-PA3{slash}USART2_RX{slash}TIM5_CH4{slash}TIM9_CH2{slash}TIM2_CH4{slash}OTG_HS_ULPI_D0-Pad26)") (class "Default")
      (node (ref "U4") (pin "26") (pinfunction "PA3/USART2_RX/TIM5_CH4/TIM9_CH2/TIM2_CH4/OTG_HS_ULPI_D0_26") (pintype "bidirectional"))
    )
    (net (code "76") (name "unconnected-(U4-PA5{slash}SPI1_SCK{slash}OTG_HS_ULPI_CK{slash}TIM2_CH1_ETR{slash}TIM8_CHIN{slash}ADC12_IN5-Pad30)") (class "Default")
      (node (ref "U4") (pin "30") (pinfunction "PA5/SPI1_SCK/OTG_HS_ULPI_CK/TIM2_CH1_ETR/TIM8_CHIN/ADC12_IN5_30") (pintype "bidirectional"))
    )
    (net (code "77") (name "unconnected-(U4-PA7{slash}SPI1_MOSI{slash}TIM8_CH1N{slash}TIM14_CH1TIM3_CH2-Pad32)") (class "Default")
      (node (ref "U4") (pin "32") (pinfunction "PA7/SPI1_MOSI/TIM8_CH1N/TIM14_CH1TIM3_CH2_32") (pintype "bidirectional"))
    )
    (net (code "78") (name "unconnected-(U4-PB0{slash}TIM3_CH3{slash}TIM8_CH2N{slash}OTG_HS_ULPI_D1{slash}ETH_MII_RXD2{slash}TIM1_CH2N{slash}-Pad35)") (class "Default")
      (node (ref "U4") (pin "35") (pinfunction "PB0/TIM3_CH3/TIM8_CH2N/OTG_HS_ULPI_D1/ETH_MII_RXD2/TIM1_CH2N/_35") (pintype "bidirectional"))
    )
    (net (code "79") (name "unconnected-(U4-PB1{slash}TIM3_CH4{slash}TIM8_CH3N{slash}OTG_HS_ULPI_D2{slash}ETH_MII_RXD3{slash}OTG_HS_INTN{slash}-Pad36)") (class "Default")
      (node (ref "U4") (pin "36") (pinfunction "PB1/TIM3_CH4/TIM8_CH3N/OTG_HS_ULPI_D2/ETH_MII_RXD3/OTG_HS_INTN/_36") (pintype "bidirectional"))
    )
    (net (code "80") (name "unconnected-(U4-PB3{slash}JTDO{slash}TRACESWO{slash}SPI3_SCK{slash}I2S3_CK{slash}TIM2_CH2{slash}SPI1_SCK-Pad89)") (class "Default")
      (node (ref "U4") (pin "89") (pinfunction "PB3/JTDO/TRACESWO/SPI3_SCK/I2S3_CK/TIM2_CH2/SPI1_SCK_89") (pintype "bidirectional"))
    )
    (net (code "81") (name "unconnected-(U4-PB4{slash}NJTRST{slash}SPI3_MISO{slash}TIM3_CH1{slash}SPI1_MISO{slash}I2S3EXT_SD-Pad90)") (class "Default")
      (node (ref "U4") (pin "90") (pinfunction "PB4/NJTRST/SPI3_MISO/TIM3_CH1/SPI1_MISO/I2S3EXT_SD_90") (pintype "bidirectional"))
    )
    (net (code "82") (name "unconnected-(U4-PB12{slash}SPI2_NSS{slash}I2S2_WS{slash}I2C2_SMBA{slash}USART3_CK{slash}TIM1_BKIN{slash}CAN2_RX-Pad51)") (class "Default")
      (node (ref "U4") (pin "51") (pinfunction "PB12/SPI2_NSS/I2S2_WS/I2C2_SMBA/USART3_CK/TIM1_BKIN/CAN2_RX_51") (pintype "bidirectional"))
    )
    (net (code "83") (name "unconnected-(U4-PB14{slash}SPI2_MISO{slash}TIM1_CH2N{slash}TIM12_CH1{slash}OTG_HS_DMUSART3_{slash}53{slash}RTS{slash}TIM8_CH2N-Pad53)") (class "Default")
      (node (ref "U4") (pin "53") (pinfunction "PB14/SPI2_MISO/TIM1_CH2N/TIM12_CH1/OTG_HS_DMUSART3_/53/RTS/TIM8_CH2N_53") (pintype "bidirectional"))
    )
    (net (code "84") (name "unconnected-(U4-PB15{slash}SPI2_MOSI{slash}I2S2_SD{slash}TIM1_CH3N{slash}TIM8_CH3N{slash}TIM12_CH2{slash}OTG_HS_DP-Pad54)") (class "Default")
      (node (ref "U4") (pin "54") (pinfunction "PB15/SPI2_MOSI/I2S2_SD/TIM1_CH3N/TIM8_CH3N/TIM12_CH2/OTG_HS_DP_54") (pintype "bidirectional"))
    )
    (net (code "85") (name "unconnected-(U4-PC4{slash}ETH_RMII_RX_D0{slash}ETH_MII_RX_D0{slash}ADC12_IN14-Pad33)") (class "Default")
      (node (ref "U4") (pin "33") (pinfunction "PC4/ETH_RMII_RX_D0/ETH_MII_RX_D0/ADC12_IN14_33") (pintype "bidirectional"))
    )
    (net (code "86") (name "unconnected-(U4-PC5{slash}ETH_RMII_RX_D1{slash}ETH_MII_RX_D1{slash}ADC12_IN15-Pad34)") (class "Default")
      (node (ref "U4") (pin "34") (pinfunction "PC5/ETH_RMII_RX_D1/ETH_MII_RX_D1/ADC12_IN15_34") (pintype "bidirectional"))
    )
    (net (code "87") (name "unconnected-(U4-PC13{slash}RTC_AF1-Pad7)") (class "Default")
      (node (ref "U4") (pin "7") (pinfunction "PC13/RTC_AF1_7") (pintype "bidirectional"))
    )
    (net (code "88") (name "unconnected-(U4-PC14{slash}OSC32_IN-Pad8)") (class "Default")
      (node (ref "U4") (pin "8") (pinfunction "PC14/OSC32_IN_8") (pintype "bidirectional"))
    )
    (net (code "89") (name "unconnected-(U4-PC15{slash}OSC32_OUT-Pad9)") (class "Default")
      (node (ref "U4") (pin "9") (pinfunction "PC15/OSC32_OUT_9") (pintype "bidirectional"))
    )
    (net (code "90") (name "unconnected-(U4-PD0{slash}FSMC_D2{slash}CAN1_RX-Pad81)") (class "Default")
      (node (ref "U4") (pin "81") (pinfunction "PD0/FSMC_D2/CAN1_RX_81") (pintype "bidirectional"))
    )
    (net (code "91") (name "unconnected-(U4-PD1FSMC_D3{slash}CAN1_TX-Pad82)") (class "Default")
      (node (ref "U4") (pin "82") (pinfunction "PD1FSMC_D3/CAN1_TX_82") (pintype "bidirectional"))
    )
    (net (code "92") (name "unconnected-(U4-PD2{slash}TIM3_ETR{slash}UART5_RXSDIO_CMD{slash}DCMI_D11-Pad83)") (class "Default")
      (node (ref "U4") (pin "83") (pinfunction "PD2/TIM3_ETR/UART5_RXSDIO_CMD/DCMI_D11_83") (pintype "bidirectional"))
    )
    (net (code "93") (name "unconnected-(U4-PD3{slash}FSMC_CLK{slash}USART2_CTS-Pad84)") (class "Default")
      (node (ref "U4") (pin "84") (pinfunction "PD3/FSMC_CLK/USART2_CTS_84") (pintype "bidirectional"))
    )
    (net (code "94") (name "unconnected-(U4-PD7{slash}USART2_CK{slash}FSMC_NE1{slash}FSMC_NCE2-Pad88)") (class "Default")
      (node (ref "U4") (pin "88") (pinfunction "PD7/USART2_CK/FSMC_NE1/FSMC_NCE2_88") (pintype "bidirectional"))
    )
    (net (code "95") (name "unconnected-(U4-PD8{slash}FSMC_D13{slash}USART3_TX-Pad55)") (class "Default")
      (node (ref "U4") (pin "55") (pinfunction "PD8/FSMC_D13/USART3_TX_55") (pintype "bidirectional"))
    )
    (net (code "96") (name "unconnected-(U4-PD9{slash}FSMC_D14{slash}USART3_RX-Pad56)") (class "Default")
      (node (ref "U4") (pin "56") (pinfunction "PD9/FSMC_D14/USART3_RX_56") (pintype "bidirectional"))
    )
    (net (code "97") (name "unconnected-(U4-PD10{slash}FSMC_D15{slash}USART3_CK-Pad57)") (class "Default")
      (node (ref "U4") (pin "57") (pinfunction "PD10/FSMC_D15/USART3_CK_57") (pintype "bidirectional"))
    )
    (net (code "98") (name "unconnected-(U4-PD11{slash}FSMC_A16{slash}USART3_CTS-Pad58)") (class "Default")
      (node (ref "U4") (pin "58") (pinfunction "PD11/FSMC_A16/USART3_CTS_58") (pintype "bidirectional"))
    )
    (net (code "99") (name "unconnected-(U4-PD12{slash}FSMC_A17{slash}TIM4_CH1{slash}USART3_RTS-Pad59)") (class "Default")
      (node (ref "U4") (pin "59") (pinfunction "PD12/FSMC_A17/TIM4_CH1/USART3_RTS_59") (pintype "bidirectional"))
    )
    (net (code "100") (name "unconnected-(U4-PD13{slash}FSMC_A18{slash}TIM4_CH2-Pad60)") (class "Default")
      (node (ref "U4") (pin "60") (pinfunction "PD13/FSMC_A18/TIM4_CH2_60") (pintype "bidirectional"))
    )
    (net (code "101") (name "unconnected-(U4-PD14{slash}FSMC_D0{slash}TIM4_CH3-Pad61)") (class "Default")
      (node (ref "U4") (pin "61") (pinfunction "PD14/FSMC_D0/TIM4_CH3_61") (pintype "bidirectional"))
    )
    (net (code "102") (name "unconnected-(U4-PD15{slash}FSMC_D1{slash}TIM4_CH4-Pad62)") (class "Default")
      (node (ref "U4") (pin "62") (pinfunction "PD15/FSMC_D1/TIM4_CH4_62") (pintype "bidirectional"))
    )
    (net (code "103") (name "unconnected-(U4-PE2{slash}TRACECLK{slash}FSMC_A23{slash}ETH_MII_TXD3-Pad1)") (class "Default")
      (node (ref "U4") (pin "1") (pinfunction "PE2/TRACECLK/FSMC_A23/ETH_MII_TXD3_1") (pintype "bidirectional"))
    )
    (net (code "104") (name "unconnected-(U4-PE3{slash}TRACED0{slash}FSMC_A19-Pad2)") (class "Default")
      (node (ref "U4") (pin "2") (pinfunction "PE3/TRACED0/FSMC_A19_2") (pintype "bidirectional"))
    )
    (net (code "105") (name "unconnected-(U4-PE7{slash}FSMC_D4{slash}TIM1_ETR-Pad38)") (class "Default")
      (node (ref "U4") (pin "38") (pinfunction "PE7/FSMC_D4/TIM1_ETR_38") (pintype "bidirectional"))
    )
    (net (code "106") (name "unconnected-(U4-PE8{slash}FSMC_D5{slash}TIM1_CH1N-Pad39)") (class "Default")
      (node (ref "U4") (pin "39") (pinfunction "PE8/FSMC_D5/TIM1_CH1N_39") (pintype "bidirectional"))
    )
    (net (code "107") (name "unconnected-(U4-PE10{slash}FSMC_D7{slash}TIM1_CH2N-Pad41)") (class "Default")
      (node (ref "U4") (pin "41") (pinfunction "PE10/FSMC_D7/TIM1_CH2N_41") (pintype "bidirectional"))
    )
    (net (code "108") (name "unconnected-(U4-PE11{slash}FSMC_D8{slash}TIM1_CH2-Pad42)") (class "Default")
      (node (ref "U4") (pin "42") (pinfunction "PE11/FSMC_D8/TIM1_CH2_42") (pintype "bidirectional"))
    )
    (net (code "109") (name "unconnected-(U4-PE12{slash}FSMC_D9{slash}TIM1_CH3N-Pad43)") (class "Default")
      (node (ref "U4") (pin "43") (pinfunction "PE12/FSMC_D9/TIM1_CH3N_43") (pintype "bidirectional"))
    )
    (net (code "110") (name "unconnected-(U4-PE13{slash}FSMC_D10{slash}TIM1_CH3-Pad44)") (class "Default")
      (node (ref "U4") (pin "44") (pinfunction "PE13/FSMC_D10/TIM1_CH3_44") (pintype "bidirectional"))
    )
    (net (code "111") (name "unconnected-(U4-PE14{slash}FSMC_D11{slash}TIM1_CH4-Pad45)") (class "Default")
      (node (ref "U4") (pin "45") (pinfunction "PE14/FSMC_D11/TIM1_CH4_45") (pintype "bidirectional"))
    )
    (net (code "112") (name "unconnected-(U4-PE15FSMC_D12{slash}TIM1_BKIN-Pad46)") (class "Default")
      (node (ref "U4") (pin "46") (pinfunction "PE15FSMC_D12/TIM1_BKIN_46") (pintype "bidirectional"))
    )
    (net (code "113") (name "unconnected-(X1-GND1-PadMT1)") (class "Default")
      (node (ref "X1") (pin "MT1") (pinfunction "GND1_MT1") (pintype "passive"))
    )
    (net (code "114") (name "unconnected-(X1-GND2-PadMT2)") (class "Default")
      (node (ref "X1") (pin "MT2") (pinfunction "GND2_MT2") (pintype "passive"))
    )
    (net (code "115") (name "unconnected-(X1-GND3-PadMT5)") (class "Default")
      (node (ref "X1") (pin "MT5") (pinfunction "GND3_MT5") (pintype "passive"))
    )
    (net (code "116") (name "unconnected-(X1-GND4-PadMT6)") (class "Default")
      (node (ref "X1") (pin "MT6") (pinfunction "GND4_MT6") (pintype "passive"))
    )
  )
)
